# LAB-PLR5010D.net
KiCad netlist of a schematic drawn in EAGLE
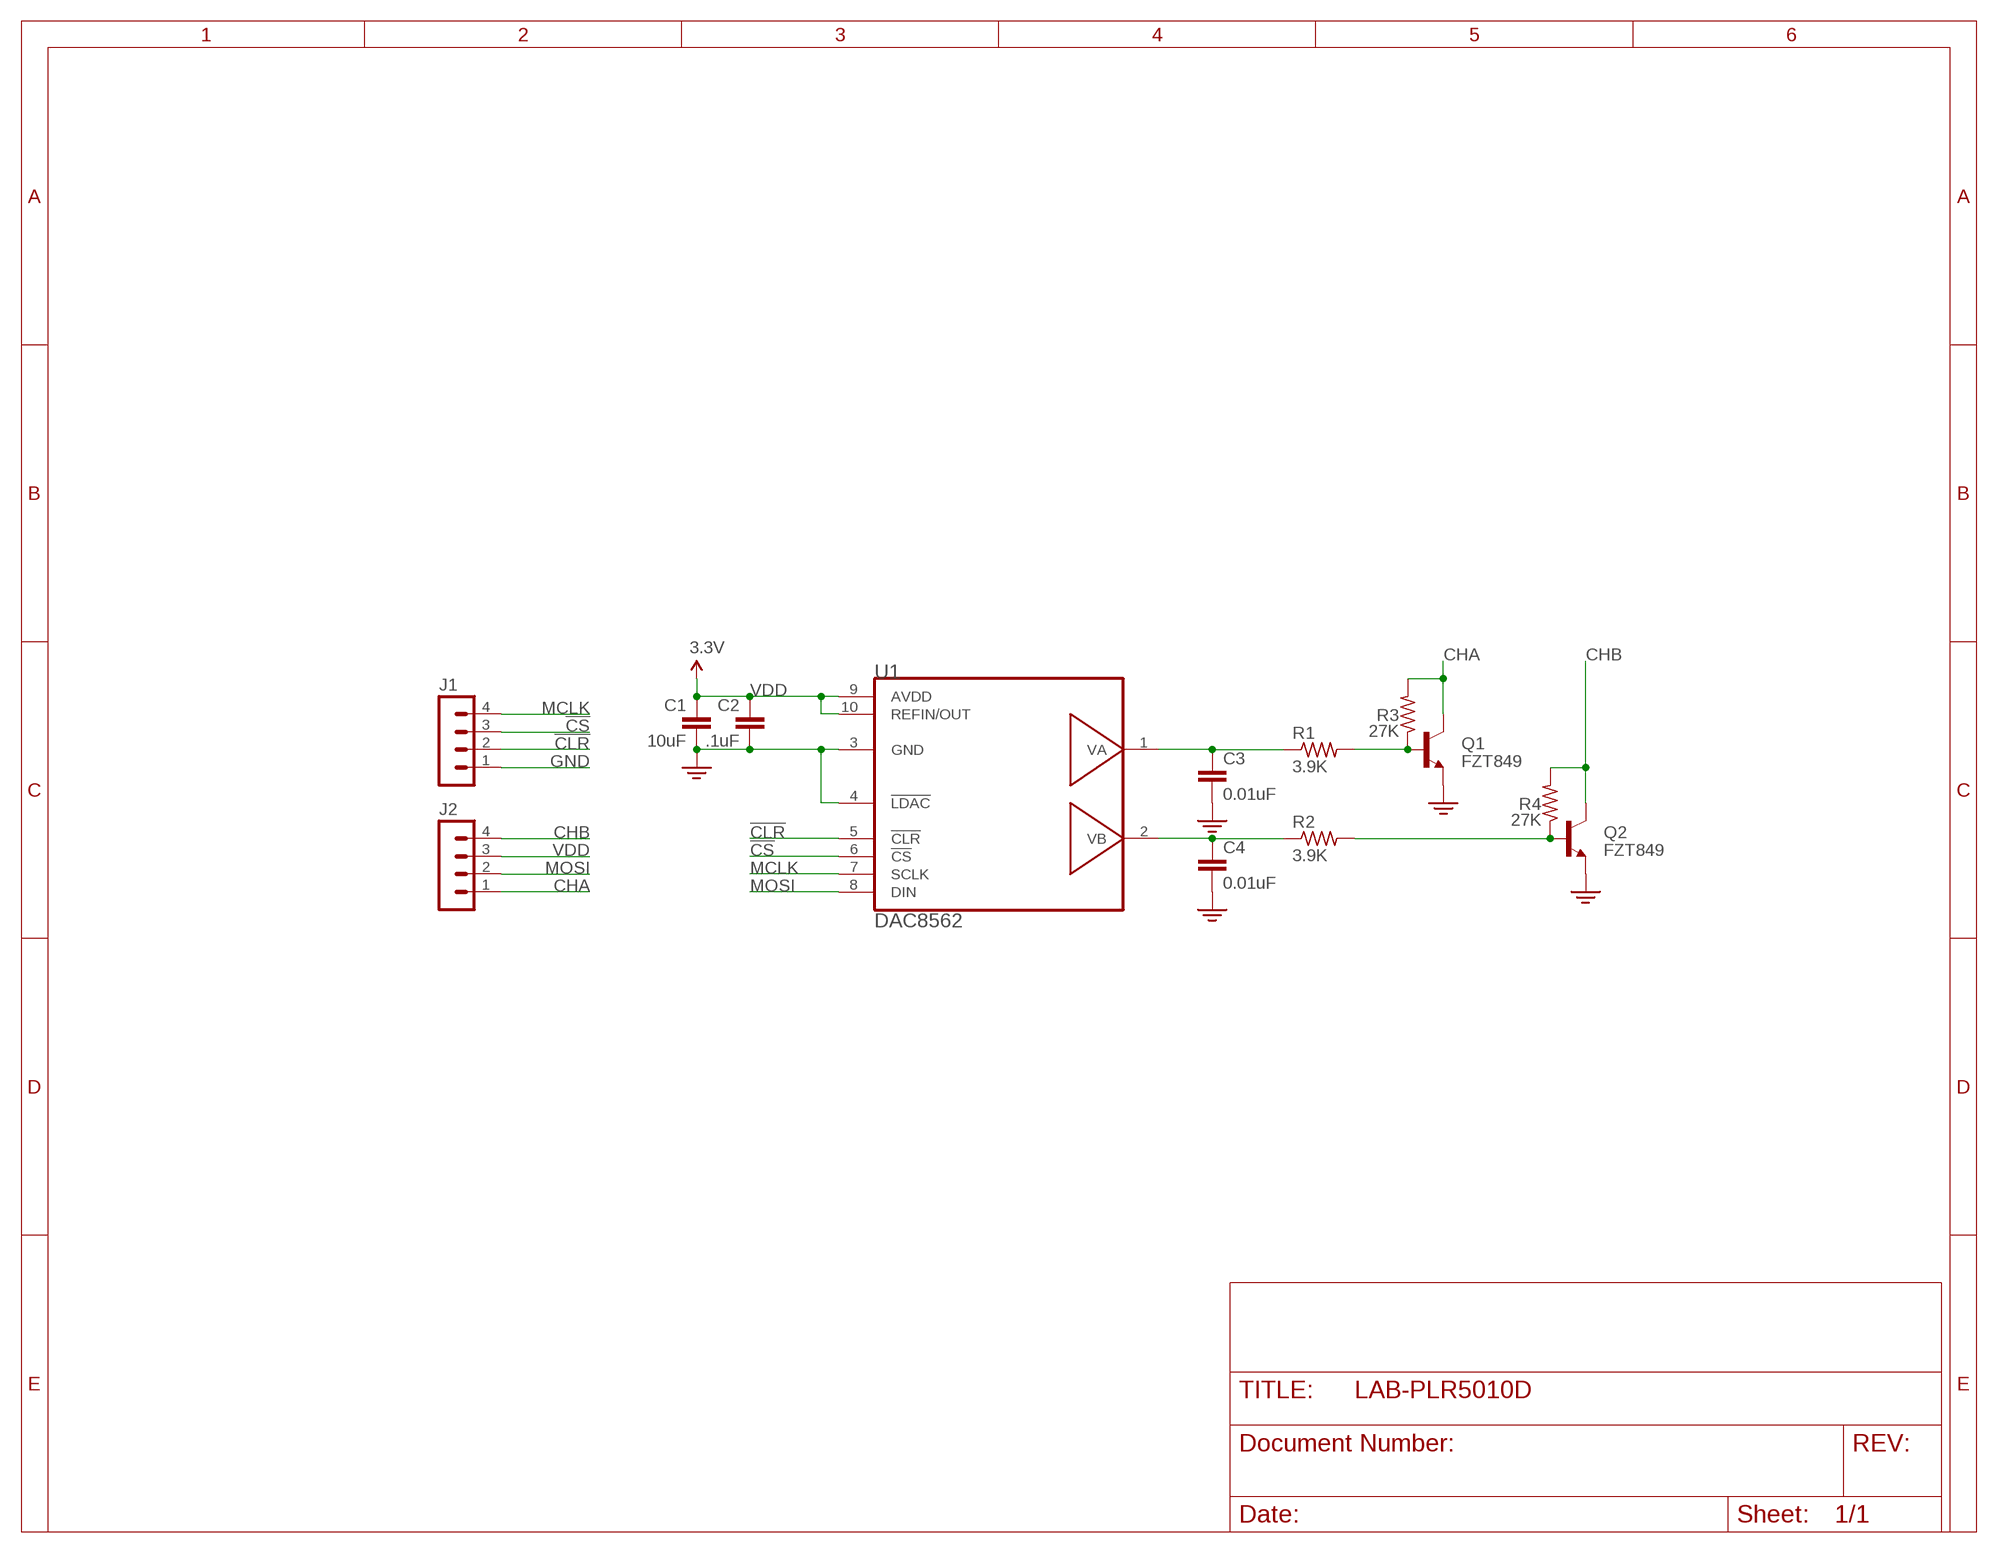
[diagram p0: schematic, sheet 1]

(export (version "E")
  (design (tool "Eeschema 10.0.6"))
  (components
    (comp (ref "C1")
      (value "10uF")
      (footprint "eagle-import:0603-CAP")
      (libsource (lib "eagle-import") (part "1NF/1000PF-50V-10%(0603)"))
    )
    (comp (ref "C2")
      (value ".1uF")
      (footprint "eagle-import:0603-CAP")
      (libsource (lib "eagle-import") (part "1NF/1000PF-50V-10%(0603)"))
    )
    (comp (ref "C3")
      (value "0.01uF")
      (footprint "eagle-import:0603-CAP")
      (libsource (lib "eagle-import") (part "1NF/1000PF-50V-10%(0603)"))
    )
    (comp (ref "C4")
      (value "0.01uF")
      (footprint "eagle-import:0603-CAP")
      (libsource (lib "eagle-import") (part "1NF/1000PF-50V-10%(0603)"))
    )
    (comp (ref "J1")
      (value "MA04-1")
      (footprint "eagle-import:MA04-1")
      (libsource (lib "eagle-import") (part "MA04-1"))
    )
    (comp (ref "J2")
      (value "MA04-1")
      (footprint "eagle-import:MA04-1")
      (libsource (lib "eagle-import") (part "MA04-1"))
    )
    (comp (ref "Q1")
      (value "FZT849")
      (footprint "eagle-import:SOT223")
      (libsource (lib "eagle-import") (part "FZT849"))
    )
    (comp (ref "Q2")
      (value "FZT849")
      (footprint "eagle-import:SOT223")
      (libsource (lib "eagle-import") (part "FZT849"))
    )
    (comp (ref "R1")
      (value "3.9K")
      (footprint "eagle-import:R0603")
      (libsource (lib "eagle-import") (part "R-US_R0603"))
    )
    (comp (ref "R2")
      (value "3.9K")
      (footprint "eagle-import:R0603")
      (libsource (lib "eagle-import") (part "R-US_R0603"))
    )
    (comp (ref "R3")
      (value "27K")
      (footprint "eagle-import:R0603")
      (libsource (lib "eagle-import") (part "R-US_R0603"))
    )
    (comp (ref "R4")
      (value "27K")
      (footprint "eagle-import:R0603")
      (libsource (lib "eagle-import") (part "R-US_R0603"))
    )
    (comp (ref "U1")
      (value "DAC8562")
      (footprint "eagle-import:MSOP10")
      (libsource (lib "eagle-import") (part "DAC8562"))
    )
  )
  (nets
    (net (code "1") (name "/CHA") (class "Default")
      (node (ref "J2") (pin "1") (pinfunction "1_1") (pintype "passive"))
      (node (ref "Q1") (pin "2") (pinfunction "C_2") (pintype "passive"))
      (node (ref "Q1") (pin "4") (pinfunction "C_4") (pintype "passive"))
      (node (ref "R3") (pin "2") (pinfunction "2_2") (pintype "passive"))
    )
    (net (code "2") (name "/CHB") (class "Default")
      (node (ref "J2") (pin "4") (pinfunction "4_4") (pintype "passive"))
      (node (ref "Q2") (pin "2") (pinfunction "C_2") (pintype "passive"))
      (node (ref "Q2") (pin "4") (pinfunction "C_4") (pintype "passive"))
      (node (ref "R4") (pin "2") (pinfunction "2_2") (pintype "passive"))
    )
    (net (code "3") (name "/MCLK") (class "Default")
      (node (ref "J1") (pin "4") (pinfunction "4_4") (pintype "passive"))
      (node (ref "U1") (pin "7") (pinfunction "SCLK_7") (pintype "input"))
    )
    (net (code "4") (name "/MOSI") (class "Default")
      (node (ref "J2") (pin "2") (pinfunction "2_2") (pintype "passive"))
      (node (ref "U1") (pin "8") (pinfunction "DIN_8") (pintype "input"))
    )
    (net (code "5") (name "/~{CLR}") (class "Default")
      (node (ref "J1") (pin "2") (pinfunction "2_2") (pintype "passive"))
      (node (ref "U1") (pin "5") (pinfunction "~{CLR}_5") (pintype "output"))
    )
    (net (code "6") (name "/~{CS}") (class "Default")
      (node (ref "J1") (pin "3") (pinfunction "3_3") (pintype "passive"))
      (node (ref "U1") (pin "6") (pinfunction "~{CS}_6") (pintype "input"))
    )
    (net (code "7") (name "3.3V") (class "Default")
      (node (ref "C1") (pin "1") (pinfunction "1_1") (pintype "passive"))
      (node (ref "C2") (pin "1") (pinfunction "1_1") (pintype "passive"))
      (node (ref "J2") (pin "3") (pinfunction "3_3") (pintype "passive"))
      (node (ref "U1") (pin "10") (pinfunction "REFIN/OUT_10") (pintype "bidirectional"))
      (node (ref "U1") (pin "9") (pinfunction "AVDD_9") (pintype "power_in"))
    )
    (net (code "8") (name "Net-(Q1-B)") (class "Default")
      (node (ref "Q1") (pin "1") (pinfunction "B_1") (pintype "passive"))
      (node (ref "R1") (pin "2") (pinfunction "2_2") (pintype "passive"))
      (node (ref "R3") (pin "1") (pinfunction "1_1") (pintype "passive"))
    )
    (net (code "9") (name "Net-(Q2-B)") (class "Default")
      (node (ref "Q2") (pin "1") (pinfunction "B_1") (pintype "passive"))
      (node (ref "R2") (pin "2") (pinfunction "2_2") (pintype "passive"))
      (node (ref "R4") (pin "1") (pinfunction "1_1") (pintype "passive"))
    )
    (net (code "10") (name "Net-(U1-VA)") (class "Default")
      (node (ref "C3") (pin "1") (pinfunction "1_1") (pintype "passive"))
      (node (ref "R1") (pin "1") (pinfunction "1_1") (pintype "passive"))
      (node (ref "U1") (pin "1") (pinfunction "VA_1") (pintype "output"))
    )
    (net (code "11") (name "Net-(U1-VB)") (class "Default")
      (node (ref "C4") (pin "1") (pinfunction "1_1") (pintype "passive"))
      (node (ref "R2") (pin "1") (pinfunction "1_1") (pintype "passive"))
      (node (ref "U1") (pin "2") (pinfunction "VB_2") (pintype "output"))
    )
    (net (code "12") (name "gnd") (class "Default")
      (node (ref "C1") (pin "2") (pinfunction "2_2") (pintype "passive"))
      (node (ref "C2") (pin "2") (pinfunction "2_2") (pintype "passive"))
      (node (ref "C3") (pin "2") (pinfunction "2_2") (pintype "passive"))
      (node (ref "C4") (pin "2") (pinfunction "2_2") (pintype "passive"))
      (node (ref "J1") (pin "1") (pinfunction "1_1") (pintype "passive"))
      (node (ref "Q1") (pin "3") (pinfunction "E_3") (pintype "passive"))
      (node (ref "Q2") (pin "3") (pinfunction "E_3") (pintype "passive"))
      (node (ref "U1") (pin "3") (pinfunction "GND_3") (pintype "power_in"))
      (node (ref "U1") (pin "4") (pinfunction "~{LDAC}_4") (pintype "output"))
    )
  )
)
